# 01_POWER_SUPPLY.net
KiCad netlist of a schematic drawn in Altium Designer
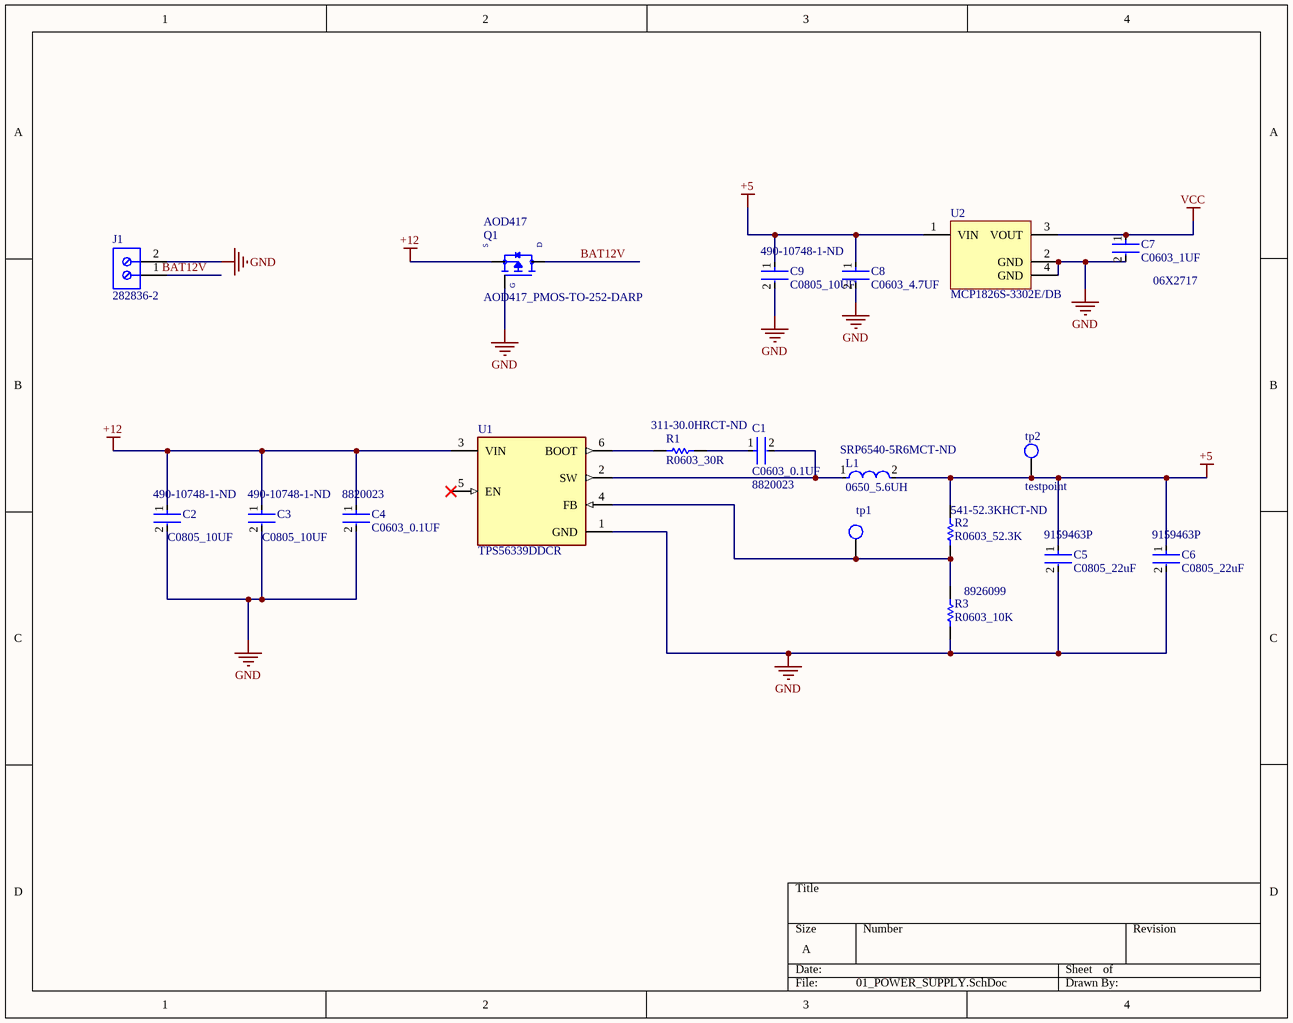
[diagram p0: 01_POWER_SUPPLY.SchDoc]

(export (version "E")
  (design (tool "Eeschema 10.0.6"))
  (components
    (comp (ref "C1")
      (value "C0603_0.1UF")
      (footprint "FP-C0603C-CF-IPC_B")
      (description "Multilayer Ceramic Capacitors MLCC Surface Mount 0603 0.1uF 50 Volts X7R 10%")
      (fields
        (field (name "SUPPLIER PART NUMBER 1") "8820023")
        (field (name "MANUFACTURER") "Murata")
        (field (name "MANUFACTURER PART NUMBER") "GRM188R71H104KA93D")
      )
      (libsource (lib "RBS_library") (part "C0603"))
    )
    (comp (ref "C2")
      (value "C0805_10UF")
      (footprint "FP-C0805C-DN-IPC_A")
      (fields
        (field (name "SUPPLIER PART NUMBER 1") "490-10748-1-ND")
        (field (name "MANUFACTURER") "Murata")
        (field (name "MANUFACTURER PART NUMBER") "GRM21BR61E106MA73L")
        (field (name "TOLERANCE") "20%")
      )
      (libsource (lib "RBS_library") (part "C0805"))
    )
    (comp (ref "C3")
      (value "C0805_10UF")
      (footprint "FP-C0805C-DN-IPC_A")
      (fields
        (field (name "SUPPLIER PART NUMBER 1") "490-10748-1-ND")
        (field (name "MANUFACTURER") "Murata")
        (field (name "MANUFACTURER PART NUMBER") "GRM21BR61E106MA73L")
        (field (name "TOLERANCE") "20%")
      )
      (libsource (lib "RBS_library") (part "C0805"))
    )
    (comp (ref "C4")
      (value "C0603_0.1UF")
      (footprint "FP-C0603C-CF-IPC_B")
      (description "Multilayer Ceramic Capacitors MLCC Surface Mount 0603 0.1uF 50 Volts X7R 10%")
      (fields
        (field (name "SUPPLIER PART NUMBER 1") "8820023")
        (field (name "MANUFACTURER") "Murata")
        (field (name "MANUFACTURER PART NUMBER") "GRM188R71H104KA93D")
      )
      (libsource (lib "RBS_library") (part "C0603"))
    )
    (comp (ref "C5")
      (value "C0805_22uF")
      (footprint "FP-C0805C-DN-IPC_A")
      (fields
        (field (name "SUPPLIER PART NUMBER 1") "9159463P")
        (field (name "MANUFACTURER") "TDK")
        (field (name "MANUFACTURER PART NUMBER") "C2012X7S1A226M125AC")
        (field (name "TOLERANCE") "20%")
      )
      (libsource (lib "RBS_library") (part "C0805"))
    )
    (comp (ref "C6")
      (value "C0805_22uF")
      (footprint "FP-C0805C-DN-IPC_A")
      (fields
        (field (name "SUPPLIER PART NUMBER 1") "9159463P")
        (field (name "MANUFACTURER") "TDK")
        (field (name "MANUFACTURER PART NUMBER") "C2012X7S1A226M125AC")
        (field (name "TOLERANCE") "20%")
      )
      (libsource (lib "RBS_library") (part "C0805"))
    )
    (comp (ref "C7")
      (value "C0603_1UF")
      (footprint "FP-C0603C-CF-IPC_B")
      (description "0603 1 uF 50 V ±10% Tolerance X5R Surface Mount Multilayer Ceramic Capacitor")
      (fields
        (field (name "SUPPLIER PART NUMBER 1") "06X2717")
        (field (name "MANUFACTURER") "Taiyo Yuden")
        (field (name "MANUFACTURER PART NUMBER") "UMK107BJ105KA-T")
      )
      (libsource (lib "RBS_library") (part "C0603"))
    )
    (comp (ref "C8")
      (value "C0603_4.7UF")
      (footprint "FP-C0603C-CF-IPC_B")
      (description "CAP CER 4.7UF 0603")
      (fields
        (field (name "MANUFACTURER") "Murata")
        (field (name "MANUFACTURER PART NUMBER") "GRM155R60J475ME47D")
      )
      (libsource (lib "RBS_library") (part "C0603"))
    )
    (comp (ref "C9")
      (value "C0805_10UF")
      (footprint "FP-C0805C-DN-IPC_A")
      (fields
        (field (name "SUPPLIER PART NUMBER 1") "490-10748-1-ND")
        (field (name "MANUFACTURER") "Murata")
        (field (name "MANUFACTURER PART NUMBER") "GRM21BR61E106MA73L")
        (field (name "TOLERANCE") "20%")
      )
      (libsource (lib "RBS_library") (part "C0805"))
    )
    (comp (ref "J1")
      (value "282836-2")
      (footprint "TECO-282836-2_V")
      (description "Female Header, Pitch 5 mm, 1 x 2 Position, Height 10 mm, Tail Length 3.5 mm, Rohs, Bulk")
      (fields (field (name "VOLTAGE") "300V") (field (name "MANUFACTURER") "TE Connectivity"))
      (libsource (lib "Altium Content Vault") (part "CN-1P-F-TB2"))
    )
    (comp (ref "L1")
      (value "0650_5.6UH")
      (footprint "FP-SRP6540-MFG")
      (description "0650_5.6UH, made in china")
      (fields
        (field (name "SUPPLIER PART NUMBER 1") "SRP6540-5R6MCT-ND")
        (field (name "MANUFACTURER") "Bourns")
        (field (name "MANUFACTURER PART NUMBER") "SRP6540-5R6M")
      )
      (libsource (lib "RBS_library") (part "SRP6540"))
    )
    (comp (ref "Q1")
      (value "AOD417_PMOS-TO-252-DARP")
      (footprint "DPAK228P994X240_3N")
      (description "Trans MOSFET P-CH 30V 25A 3-Pin(2+Tab) DPAK")
      (fields
        (field (name "SUPPLIER PART NUMBER 1") "AOD417")
        (field (name "MANUFACTURER") "Alpha & Omega Semiconductor")
        (field (name "MANUFACTURER PART NUMBER") "AOD417")
      )
      (libsource (lib "RBS_library") (part "PMOS"))
    )
    (comp (ref "R1")
      (value "R0603_30R")
      (footprint "RESC1609X55X30LL15T15")
      (fields
        (field (name "SUPPLIER PART NUMBER 1") "311-30.0HRCT-ND")
        (field (name "MANUFACTURER") "Yageo")
        (field (name "MANUFACTURER PART NUMBER") "RC0603FR-0730RL")
        (field (name "TOLERANCE") "1%")
      )
      (libsource (lib "RBS_library") (part "R0603"))
    )
    (comp (ref "R2")
      (value "R0603_52.3K")
      (footprint "RESC1609X55X30LL15T15")
      (description "Res Thick Film 0603 52.3K Ohm 1% 0.1W(1/10W) ±100ppm/C Pad SMD Automotive T/R")
      (fields
        (field (name "SUPPLIER PART NUMBER 1") "541-52.3KHCT-ND")
        (field (name "MANUFACTURER") "Vishay")
        (field (name "MANUFACTURER PART NUMBER") "CRCW060352K3FKEA")
      )
      (libsource (lib "RBS_library") (part "R0603"))
    )
    (comp (ref "R3")
      (value "R0603_10K")
      (footprint "RESC1609X55X30LL15T15")
      (description "VISHAY - CRCW060310K0FKEA - RES, THICK FILM, 10K, 1%, 0.1W, 0603")
      (fields
        (field (name "SUPPLIER PART NUMBER 1") "8926099")
        (field (name "MANUFACTURER") "Vishay")
        (field (name "MANUFACTURER PART NUMBER") "CRCW060310K0FKEA")
      )
      (libsource (lib "RBS_library") (part "R0603"))
    )
    (comp (ref "tp1")
      (value "testpoint")
      (footprint "testpoint_1mm")
      (libsource (lib "RBS_library") (part "testpoint"))
    )
    (comp (ref "tp2")
      (value "testpoint")
      (footprint "testpoint_1mm")
      (libsource (lib "RBS_library") (part "testpoint"))
    )
    (comp (ref "U1")
      (value "TPS56339DDCR")
      (footprint "FP-DDC0006A-MFG")
      (description "PWR MGMT SPECIALIZED REGULATOR")
      (fields
        (field (name "MANUFACTURER") "Texas Instruments")
        (field (name "OCTOPART") "https://octopart.com/tps56339ddcr-texas+instruments-101466410")
      )
      (libsource (lib "Altium Content Vault") (part "2ef13c8a92b2ccd2de8c1984d71b5d5"))
    )
    (comp (ref "U2")
      (value "MCP1826S-3302E/DB")
      (footprint "SOT-223-DB3_L")
      (description "1000 mA, Low Voltage, Low Quiescent Current LDO Regulator, 3-Pin SOT-223, Extended Temperature")
      (libsource (lib "Altium Content Vault") (part "PM-LINEREG-MCP1826-IL4"))
    )
  )
  (nets
    (net (code "1") (name "+5") (class "Default")
      (node (ref "C5") (pin "1") (pinfunction "1_1") (pintype "passive"))
      (node (ref "C6") (pin "1") (pinfunction "1_1") (pintype "passive"))
      (node (ref "C8") (pin "1") (pinfunction "1_1") (pintype "passive"))
      (node (ref "C9") (pin "1") (pinfunction "1_1") (pintype "passive"))
      (node (ref "L1") (pin "2") (pinfunction "2_2") (pintype "passive"))
      (node (ref "R2") (pin "2") (pinfunction "2_2") (pintype "passive"))
      (node (ref "U2") (pin "1") (pinfunction "VIN_1") (pintype "power_in"))
      (node (ref "tp2") (pin "1") (pinfunction "1_1") (pintype "passive"))
    )
    (net (code "2") (name "+12") (class "Default")
      (node (ref "C2") (pin "1") (pinfunction "1_1") (pintype "passive"))
      (node (ref "C3") (pin "1") (pinfunction "1_1") (pintype "passive"))
      (node (ref "C4") (pin "1") (pinfunction "1_1") (pintype "passive"))
      (node (ref "Q1") (pin "3") (pinfunction "S_3") (pintype "passive"))
      (node (ref "U1") (pin "3") (pinfunction "VIN_3") (pintype "power_in"))
    )
    (net (code "3") (name "/BAT12V") (class "Default")
      (node (ref "J1") (pin "1") (pinfunction "1_1") (pintype "passive"))
      (node (ref "Q1") (pin "4") (pinfunction "D_4") (pintype "passive"))
    )
    (net (code "4") (name "GND") (class "Default")
      (node (ref "C2") (pin "2") (pinfunction "2_2") (pintype "passive"))
      (node (ref "C3") (pin "2") (pinfunction "2_2") (pintype "passive"))
      (node (ref "C4") (pin "2") (pinfunction "2_2") (pintype "passive"))
      (node (ref "C5") (pin "2") (pinfunction "2_2") (pintype "passive"))
      (node (ref "C6") (pin "2") (pinfunction "2_2") (pintype "passive"))
      (node (ref "C7") (pin "2") (pinfunction "2_2") (pintype "passive"))
      (node (ref "C8") (pin "2") (pinfunction "2_2") (pintype "passive"))
      (node (ref "C9") (pin "2") (pinfunction "2_2") (pintype "passive"))
      (node (ref "J1") (pin "2") (pinfunction "2_2") (pintype "passive"))
      (node (ref "Q1") (pin "1") (pinfunction "G_1") (pintype "passive"))
      (node (ref "R3") (pin "1") (pinfunction "1_1") (pintype "passive"))
      (node (ref "U1") (pin "1") (pinfunction "GND_1") (pintype "power_in"))
      (node (ref "U2") (pin "2") (pinfunction "GND_2") (pintype "power_in"))
      (node (ref "U2") (pin "4") (pinfunction "GND_4") (pintype "power_in"))
    )
    (net (code "5") (name "Net-(C1-Pad1)") (class "Default")
      (node (ref "C1") (pin "1") (pinfunction "1_1") (pintype "passive"))
      (node (ref "R1") (pin "2") (pinfunction "2_2") (pintype "passive"))
    )
    (net (code "6") (name "Net-(U1-BOOT)") (class "Default")
      (node (ref "R1") (pin "1") (pinfunction "1_1") (pintype "passive"))
      (node (ref "U1") (pin "6") (pinfunction "BOOT_6") (pintype "output"))
    )
    (net (code "7") (name "Net-(U1-FB)") (class "Default")
      (node (ref "R2") (pin "1") (pinfunction "1_1") (pintype "passive"))
      (node (ref "R3") (pin "2") (pinfunction "2_2") (pintype "passive"))
      (node (ref "U1") (pin "4") (pinfunction "FB_4") (pintype "input"))
      (node (ref "tp1") (pin "1") (pinfunction "1_1") (pintype "passive"))
    )
    (net (code "8") (name "Net-(U1-SW)") (class "Default")
      (node (ref "C1") (pin "2") (pinfunction "2_2") (pintype "passive"))
      (node (ref "L1") (pin "1") (pinfunction "1_1") (pintype "passive"))
      (node (ref "U1") (pin "2") (pinfunction "SW_2") (pintype "output"))
    )
    (net (code "9") (name "VCC") (class "Default")
      (node (ref "C7") (pin "1") (pinfunction "1_1") (pintype "passive"))
      (node (ref "U2") (pin "3") (pinfunction "VOUT_3") (pintype "power_in"))
    )
    (net (code "10") (name "unconnected-(U1-EN-Pad5)") (class "Default")
      (node (ref "U1") (pin "5") (pinfunction "EN_5") (pintype "input+no_connect"))
    )
  )
)
